# windsensor-esp12-v002.net
KiCad netlist of a schematic drawn in EAGLE
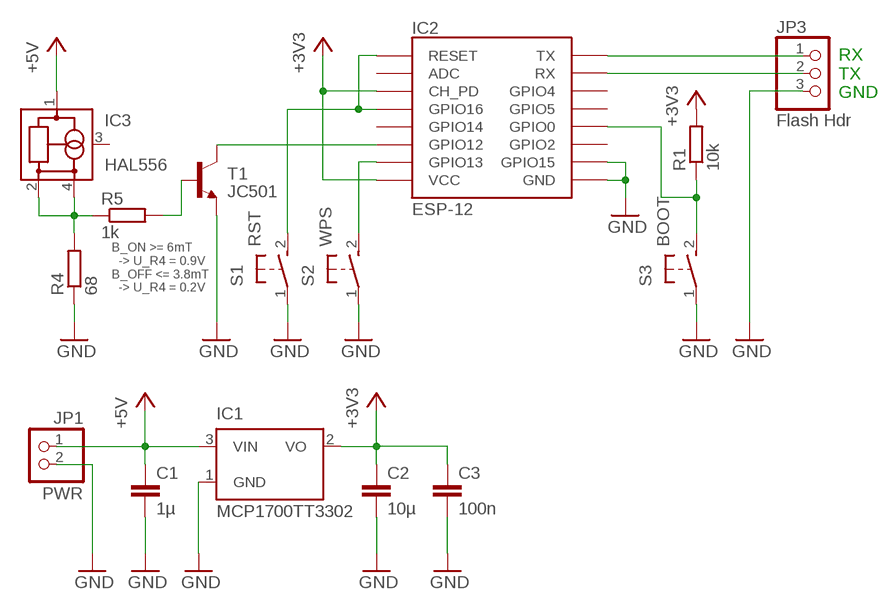
[diagram p0: schematic, sheet 1]

(export (version "E")
  (design (tool "Eeschema 10.0.6"))
  (components
    (comp (ref "C1")
      (value "1µ")
      (footprint "eagle-import:C0805")
      (libsource (lib "eagle-import") (part "C-EUC0805"))
    )
    (comp (ref "C2")
      (value "10µ")
      (footprint "eagle-import:C0805")
      (libsource (lib "eagle-import") (part "C-EUC0805"))
    )
    (comp (ref "C3")
      (value "100n")
      (footprint "eagle-import:C0805")
      (libsource (lib "eagle-import") (part "C-EUC0805"))
    )
    (comp (ref "IC1")
      (value "MCP1700TT3302")
      (footprint "eagle-import:SOT23")
      (libsource (lib "eagle-import") (part "MCP1700TT"))
    )
    (comp (ref "IC2")
      (value "ESP-12")
      (footprint "eagle-import:ESP-12")
      (libsource (lib "eagle-import") (part "ESP-12"))
    )
    (comp (ref "IC3")
      (value "HAL556")
      (footprint "eagle-import:SOT89")
      (libsource (lib "eagle-import") (part "HAL556"))
    )
    (comp (ref "JP1")
      (value "PWR")
      (footprint "eagle-import:1X02")
      (libsource (lib "eagle-import") (part "PINHD-1X2"))
    )
    (comp (ref "JP3")
      (value "Flash Hdr")
      (footprint "eagle-import:1X03")
      (libsource (lib "eagle-import") (part "PINHD-1X3"))
    )
    (comp (ref "R1")
      (value "10k")
      (footprint "eagle-import:R0805HS")
      (libsource (lib "eagle-import") (part "R-EU_R0805HS"))
    )
    (comp (ref "R4")
      (value "68")
      (footprint "eagle-import:R0805HS")
      (libsource (lib "eagle-import") (part "R-EU_R0805HS"))
    )
    (comp (ref "R5")
      (value "1k")
      (footprint "eagle-import:R0805HS2")
      (libsource (lib "eagle-import") (part "R-EU_R0805HS2"))
    )
    (comp (ref "S1")
      (value "RST")
      (footprint "eagle-import:TS1")
      (libsource (lib "eagle-import") (part "TS1"))
    )
    (comp (ref "S2")
      (value "WPS")
      (footprint "eagle-import:TS1")
      (libsource (lib "eagle-import") (part "TS1"))
    )
    (comp (ref "S3")
      (value "BOOT")
      (footprint "eagle-import:TS1")
      (libsource (lib "eagle-import") (part "TS1"))
    )
    (comp (ref "T1")
      (value "JC501")
      (footprint "eagle-import:TO92-ECB")
      (libsource (lib "eagle-import") (part "JC501"))
    )
  )
  (nets
    (net (code "1") (name "+3V3") (class "Default")
      (node (ref "C2") (pin "1") (pinfunction "1_1") (pintype "passive"))
      (node (ref "C3") (pin "1") (pinfunction "1_1") (pintype "passive"))
      (node (ref "IC1") (pin "2") (pinfunction "VO_2") (pintype "output"))
      (node (ref "IC2") (pin "CH_PD") (pinfunction "CH_PD_CH_PD") (pintype "bidirectional"))
      (node (ref "IC2") (pin "VCC") (pinfunction "VCC_VCC") (pintype "bidirectional"))
      (node (ref "R1") (pin "2") (pinfunction "2_2") (pintype "passive"))
    )
    (net (code "2") (name "+5V") (class "Default")
      (node (ref "C1") (pin "1") (pinfunction "1_1") (pintype "passive"))
      (node (ref "IC1") (pin "3") (pinfunction "VIN_3") (pintype "input"))
      (node (ref "IC3") (pin "1") (pinfunction "1_1") (pintype "passive"))
      (node (ref "JP1") (pin "1") (pinfunction "1_1") (pintype "passive"))
    )
    (net (code "3") (name "GND") (class "Default")
      (node (ref "C1") (pin "2") (pinfunction "2_2") (pintype "passive"))
      (node (ref "C2") (pin "2") (pinfunction "2_2") (pintype "passive"))
      (node (ref "C3") (pin "2") (pinfunction "2_2") (pintype "passive"))
      (node (ref "IC1") (pin "1") (pinfunction "GND_1") (pintype "passive"))
      (node (ref "IC2") (pin "GND") (pinfunction "GND_GND") (pintype "bidirectional"))
      (node (ref "IC2") (pin "GPIO15") (pinfunction "GPIO15_GPIO15") (pintype "bidirectional"))
      (node (ref "JP1") (pin "2") (pinfunction "2_2") (pintype "passive"))
      (node (ref "JP3") (pin "3") (pinfunction "3_3") (pintype "passive"))
      (node (ref "R4") (pin "1") (pinfunction "1_1") (pintype "passive"))
      (node (ref "S1") (pin "1") (pinfunction "1_1") (pintype "passive"))
      (node (ref "S2") (pin "1") (pinfunction "1_1") (pintype "passive"))
      (node (ref "S3") (pin "1") (pinfunction "1_1") (pintype "passive"))
      (node (ref "T1") (pin "E") (pinfunction "E_E") (pintype "passive"))
    )
    (net (code "4") (name "Net-(IC2-PadGPIO0)") (class "Default")
      (node (ref "IC2") (pin "GPIO0") (pinfunction "GPIO0_GPIO0") (pintype "bidirectional"))
      (node (ref "R1") (pin "1") (pinfunction "1_1") (pintype "passive"))
      (node (ref "S3") (pin "2") (pinfunction "2_2") (pintype "passive"))
    )
    (net (code "5") (name "Net-(IC2-PadGPIO12)") (class "Default")
      (node (ref "IC2") (pin "GPIO12") (pinfunction "GPIO12_GPIO12") (pintype "bidirectional"))
      (node (ref "T1") (pin "C") (pinfunction "C_C") (pintype "passive"))
    )
    (net (code "6") (name "Net-(IC2-PadGPIO13)") (class "Default")
      (node (ref "IC2") (pin "GPIO13") (pinfunction "GPIO13_GPIO13") (pintype "bidirectional"))
      (node (ref "S2") (pin "2") (pinfunction "2_2") (pintype "passive"))
    )
    (net (code "7") (name "Net-(IC2-PadGPIO16)") (class "Default")
      (node (ref "IC2") (pin "GPIO16") (pinfunction "GPIO16_GPIO16") (pintype "bidirectional"))
      (node (ref "IC2") (pin "RESET") (pinfunction "RESET_RESET") (pintype "bidirectional"))
      (node (ref "S1") (pin "2") (pinfunction "2_2") (pintype "passive"))
    )
    (net (code "8") (name "Net-(IC2-PadRX)") (class "Default")
      (node (ref "IC2") (pin "RX") (pinfunction "RX_RX") (pintype "bidirectional"))
      (node (ref "JP3") (pin "2") (pinfunction "2_2") (pintype "passive"))
    )
    (net (code "9") (name "Net-(IC2-PadTX)") (class "Default")
      (node (ref "IC2") (pin "TX") (pinfunction "TX_TX") (pintype "bidirectional"))
      (node (ref "JP3") (pin "1") (pinfunction "1_1") (pintype "passive"))
    )
    (net (code "10") (name "Net-(IC3-Pad2)") (class "Default")
      (node (ref "IC3") (pin "2") (pinfunction "2_2") (pintype "passive"))
      (node (ref "IC3") (pin "4") (pinfunction "4_4") (pintype "passive"))
      (node (ref "R4") (pin "2") (pinfunction "2_2") (pintype "passive"))
      (node (ref "R5") (pin "1") (pinfunction "1_1") (pintype "passive"))
    )
    (net (code "11") (name "Net-(R5-Pad2)") (class "Default")
      (node (ref "R5") (pin "2") (pinfunction "2_2") (pintype "passive"))
      (node (ref "T1") (pin "B") (pinfunction "B_B") (pintype "passive"))
    )
    (net (code "12") (name "unconnected-(IC2-PadADC)") (class "Default")
      (node (ref "IC2") (pin "ADC") (pinfunction "ADC_ADC") (pintype "bidirectional"))
    )
    (net (code "13") (name "unconnected-(IC2-PadGPIO2)") (class "Default")
      (node (ref "IC2") (pin "GPIO2") (pinfunction "GPIO2_GPIO2") (pintype "bidirectional"))
    )
    (net (code "14") (name "unconnected-(IC2-PadGPIO4)") (class "Default")
      (node (ref "IC2") (pin "GPIO4") (pinfunction "GPIO4_GPIO4") (pintype "bidirectional"))
    )
    (net (code "15") (name "unconnected-(IC2-PadGPIO5)") (class "Default")
      (node (ref "IC2") (pin "GPIO5") (pinfunction "GPIO5_GPIO5") (pintype "bidirectional"))
    )
    (net (code "16") (name "unconnected-(IC2-PadGPIO14)") (class "Default")
      (node (ref "IC2") (pin "GPIO14") (pinfunction "GPIO14_GPIO14") (pintype "bidirectional"))
    )
    (net (code "17") (name "unconnected-(IC3-Pad3)") (class "Default")
      (node (ref "IC3") (pin "3") (pinfunction "3_3") (pintype "no_connect"))
    )
  )
)
